# led_test.net
KiCad netlist of a schematic drawn in EAGLE
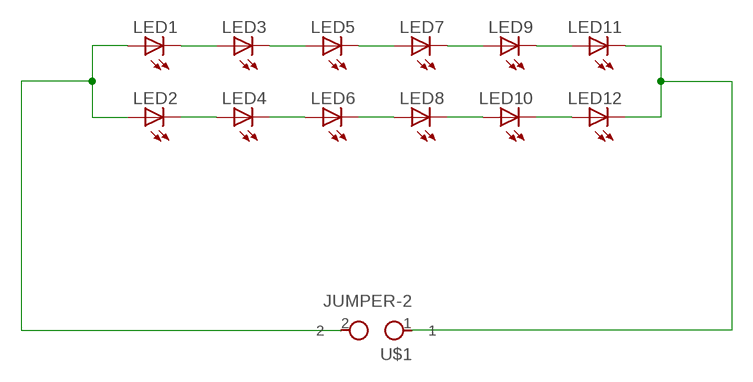
[diagram p0: schematic, sheet 1]

(export (version "E")
  (design (tool "Eeschema 10.0.6"))
  (components
    (comp (ref "LED1")
      (value "LEDCHIPLED_0603")
      (footprint "eagle-import:CHIPLED_0603")
      (libsource (lib "eagle-import") (part "LEDCHIPLED_0603"))
    )
    (comp (ref "LED2")
      (value "LEDCHIPLED_0603")
      (footprint "eagle-import:CHIPLED_0603")
      (libsource (lib "eagle-import") (part "LEDCHIPLED_0603"))
    )
    (comp (ref "LED3")
      (value "LEDCHIPLED_0603")
      (footprint "eagle-import:CHIPLED_0603")
      (libsource (lib "eagle-import") (part "LEDCHIPLED_0603"))
    )
    (comp (ref "LED4")
      (value "LEDCHIPLED_0603")
      (footprint "eagle-import:CHIPLED_0603")
      (libsource (lib "eagle-import") (part "LEDCHIPLED_0603"))
    )
    (comp (ref "LED5")
      (value "LEDCHIPLED_0603")
      (footprint "eagle-import:CHIPLED_0603")
      (libsource (lib "eagle-import") (part "LEDCHIPLED_0603"))
    )
    (comp (ref "LED6")
      (value "LEDCHIPLED_0603")
      (footprint "eagle-import:CHIPLED_0603")
      (libsource (lib "eagle-import") (part "LEDCHIPLED_0603"))
    )
    (comp (ref "LED7")
      (value "LEDCHIPLED_0603")
      (footprint "eagle-import:CHIPLED_0603")
      (libsource (lib "eagle-import") (part "LEDCHIPLED_0603"))
    )
    (comp (ref "LED8")
      (value "LEDCHIPLED_0603")
      (footprint "eagle-import:CHIPLED_0603")
      (libsource (lib "eagle-import") (part "LEDCHIPLED_0603"))
    )
    (comp (ref "LED9")
      (value "LEDCHIPLED_0603")
      (footprint "eagle-import:CHIPLED_0603")
      (libsource (lib "eagle-import") (part "LEDCHIPLED_0603"))
    )
    (comp (ref "LED10")
      (value "LEDCHIPLED_0603")
      (footprint "eagle-import:CHIPLED_0603")
      (libsource (lib "eagle-import") (part "LEDCHIPLED_0603"))
    )
    (comp (ref "LED11")
      (value "LEDCHIPLED_0603")
      (footprint "eagle-import:CHIPLED_0603")
      (libsource (lib "eagle-import") (part "LEDCHIPLED_0603"))
    )
    (comp (ref "LED12")
      (value "LEDCHIPLED_0603")
      (footprint "eagle-import:CHIPLED_0603")
      (libsource (lib "eagle-import") (part "LEDCHIPLED_0603"))
    )
    (comp (ref "U$1")
      (value "JUMPER-2")
      (footprint "eagle-import:1X02")
      (libsource (lib "eagle-import") (part "JUMPER-2"))
    )
  )
  (nets
    (net (code "1") (name "Net-(LED1-PadA)") (class "Default")
      (node (ref "LED1") (pin "A") (pinfunction "A_A") (pintype "passive"))
      (node (ref "LED2") (pin "A") (pinfunction "A_A") (pintype "passive"))
      (node (ref "U$1") (pin "2") (pinfunction "2_2") (pintype "bidirectional"))
    )
    (net (code "2") (name "Net-(LED1-PadC)") (class "Default")
      (node (ref "LED1") (pin "C") (pinfunction "C_C") (pintype "passive"))
      (node (ref "LED3") (pin "A") (pinfunction "A_A") (pintype "passive"))
    )
    (net (code "3") (name "Net-(LED2-PadC)") (class "Default")
      (node (ref "LED2") (pin "C") (pinfunction "C_C") (pintype "passive"))
      (node (ref "LED4") (pin "A") (pinfunction "A_A") (pintype "passive"))
    )
    (net (code "4") (name "Net-(LED3-PadC)") (class "Default")
      (node (ref "LED3") (pin "C") (pinfunction "C_C") (pintype "passive"))
      (node (ref "LED5") (pin "A") (pinfunction "A_A") (pintype "passive"))
    )
    (net (code "5") (name "Net-(LED4-PadC)") (class "Default")
      (node (ref "LED4") (pin "C") (pinfunction "C_C") (pintype "passive"))
      (node (ref "LED6") (pin "A") (pinfunction "A_A") (pintype "passive"))
    )
    (net (code "6") (name "Net-(LED5-PadC)") (class "Default")
      (node (ref "LED5") (pin "C") (pinfunction "C_C") (pintype "passive"))
      (node (ref "LED7") (pin "A") (pinfunction "A_A") (pintype "passive"))
    )
    (net (code "7") (name "Net-(LED6-PadC)") (class "Default")
      (node (ref "LED6") (pin "C") (pinfunction "C_C") (pintype "passive"))
      (node (ref "LED8") (pin "A") (pinfunction "A_A") (pintype "passive"))
    )
    (net (code "8") (name "Net-(LED7-PadC)") (class "Default")
      (node (ref "LED7") (pin "C") (pinfunction "C_C") (pintype "passive"))
      (node (ref "LED9") (pin "A") (pinfunction "A_A") (pintype "passive"))
    )
    (net (code "9") (name "Net-(LED10-PadA)") (class "Default")
      (node (ref "LED10") (pin "A") (pinfunction "A_A") (pintype "passive"))
      (node (ref "LED8") (pin "C") (pinfunction "C_C") (pintype "passive"))
    )
    (net (code "10") (name "Net-(LED10-PadC)") (class "Default")
      (node (ref "LED10") (pin "C") (pinfunction "C_C") (pintype "passive"))
      (node (ref "LED12") (pin "A") (pinfunction "A_A") (pintype "passive"))
    )
    (net (code "11") (name "Net-(LED11-PadA)") (class "Default")
      (node (ref "LED11") (pin "A") (pinfunction "A_A") (pintype "passive"))
      (node (ref "LED9") (pin "C") (pinfunction "C_C") (pintype "passive"))
    )
    (net (code "12") (name "Net-(LED11-PadC)") (class "Default")
      (node (ref "LED11") (pin "C") (pinfunction "C_C") (pintype "passive"))
      (node (ref "LED12") (pin "C") (pinfunction "C_C") (pintype "passive"))
      (node (ref "U$1") (pin "1") (pinfunction "1_1") (pintype "bidirectional"))
    )
  )
)
